# BreadBoard.net
KiCad netlist of a schematic drawn in Altium Designer
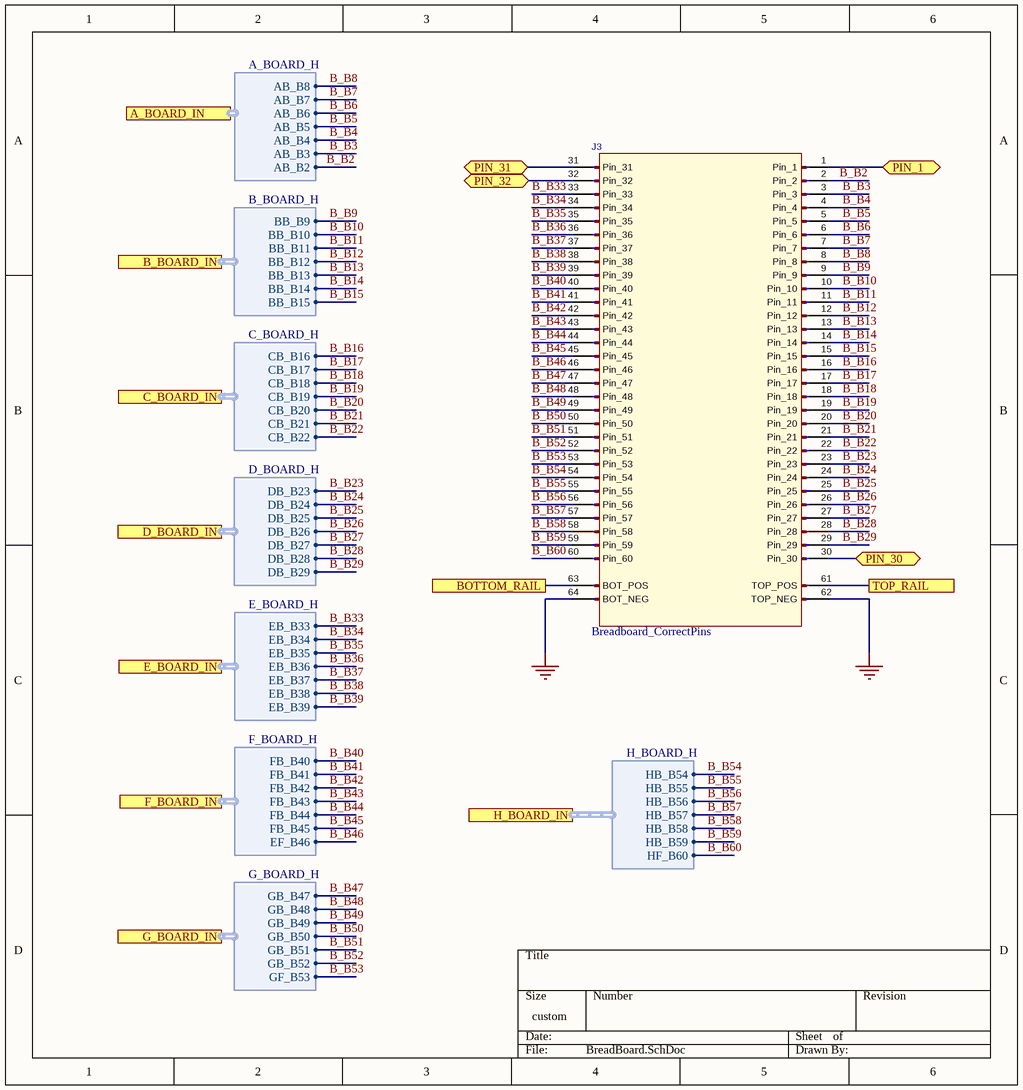
[diagram p0: BreadBoard.SchDoc]

(export (version "E")
  (design (tool "Eeschema 10.0.6"))
  (components
    (comp (ref "J3")
      (value "Breadboard_CorrectPins")
      (footprint "Breadboard_CustomClips_CorrectPins_1")
      (libsource (lib "breadboard_correctpins") (part "Breadboard_CorrectPins"))
    )
  )
  (nets
    (net (code "9") (name "/BOTTOM_RAIL") (class "Default")
      (node (ref "J3") (pin "63") (pinfunction "BOT_POS_63") (pintype "power_in"))
    )
    (net (code "10") (name "/B_B2") (class "Default")
      (node (ref "J3") (pin "2") (pinfunction "Pin_2_2") (pintype "passive"))
    )
    (net (code "11") (name "/B_B3") (class "Default")
      (node (ref "J3") (pin "3") (pinfunction "Pin_3_3") (pintype "passive"))
    )
    (net (code "12") (name "/B_B4") (class "Default")
      (node (ref "J3") (pin "4") (pinfunction "Pin_4_4") (pintype "passive"))
    )
    (net (code "13") (name "/B_B5") (class "Default")
      (node (ref "J3") (pin "5") (pinfunction "Pin_5_5") (pintype "passive"))
    )
    (net (code "14") (name "/B_B6") (class "Default")
      (node (ref "J3") (pin "6") (pinfunction "Pin_6_6") (pintype "passive"))
    )
    (net (code "15") (name "/B_B7") (class "Default")
      (node (ref "J3") (pin "7") (pinfunction "Pin_7_7") (pintype "passive"))
    )
    (net (code "16") (name "/B_B8") (class "Default")
      (node (ref "J3") (pin "8") (pinfunction "Pin_8_8") (pintype "passive"))
    )
    (net (code "17") (name "/B_B9") (class "Default")
      (node (ref "J3") (pin "9") (pinfunction "Pin_9_9") (pintype "passive"))
    )
    (net (code "18") (name "/B_B10") (class "Default")
      (node (ref "J3") (pin "10") (pinfunction "Pin_10_10") (pintype "passive"))
    )
    (net (code "19") (name "/B_B11") (class "Default")
      (node (ref "J3") (pin "11") (pinfunction "Pin_11_11") (pintype "passive"))
    )
    (net (code "20") (name "/B_B12") (class "Default")
      (node (ref "J3") (pin "12") (pinfunction "Pin_12_12") (pintype "passive"))
    )
    (net (code "21") (name "/B_B13") (class "Default")
      (node (ref "J3") (pin "13") (pinfunction "Pin_13_13") (pintype "passive"))
    )
    (net (code "22") (name "/B_B14") (class "Default")
      (node (ref "J3") (pin "14") (pinfunction "Pin_14_14") (pintype "passive"))
    )
    (net (code "23") (name "/B_B15") (class "Default")
      (node (ref "J3") (pin "15") (pinfunction "Pin_15_15") (pintype "passive"))
    )
    (net (code "24") (name "/B_B16") (class "Default")
      (node (ref "J3") (pin "16") (pinfunction "Pin_16_16") (pintype "passive"))
    )
    (net (code "25") (name "/B_B17") (class "Default")
      (node (ref "J3") (pin "17") (pinfunction "Pin_17_17") (pintype "passive"))
    )
    (net (code "26") (name "/B_B18") (class "Default")
      (node (ref "J3") (pin "18") (pinfunction "Pin_18_18") (pintype "passive"))
    )
    (net (code "27") (name "/B_B19") (class "Default")
      (node (ref "J3") (pin "19") (pinfunction "Pin_19_19") (pintype "passive"))
    )
    (net (code "28") (name "/B_B20") (class "Default")
      (node (ref "J3") (pin "20") (pinfunction "Pin_20_20") (pintype "passive"))
    )
    (net (code "29") (name "/B_B21") (class "Default")
      (node (ref "J3") (pin "21") (pinfunction "Pin_21_21") (pintype "passive"))
    )
    (net (code "30") (name "/B_B22") (class "Default")
      (node (ref "J3") (pin "22") (pinfunction "Pin_22_22") (pintype "passive"))
    )
    (net (code "31") (name "/B_B23") (class "Default")
      (node (ref "J3") (pin "23") (pinfunction "Pin_23_23") (pintype "passive"))
    )
    (net (code "32") (name "/B_B24") (class "Default")
      (node (ref "J3") (pin "24") (pinfunction "Pin_24_24") (pintype "passive"))
    )
    (net (code "33") (name "/B_B25") (class "Default")
      (node (ref "J3") (pin "25") (pinfunction "Pin_25_25") (pintype "passive"))
    )
    (net (code "34") (name "/B_B26") (class "Default")
      (node (ref "J3") (pin "26") (pinfunction "Pin_26_26") (pintype "passive"))
    )
    (net (code "35") (name "/B_B27") (class "Default")
      (node (ref "J3") (pin "27") (pinfunction "Pin_27_27") (pintype "passive"))
    )
    (net (code "36") (name "/B_B28") (class "Default")
      (node (ref "J3") (pin "28") (pinfunction "Pin_28_28") (pintype "passive"))
    )
    (net (code "37") (name "/B_B29") (class "Default")
      (node (ref "J3") (pin "29") (pinfunction "Pin_29_29") (pintype "passive"))
    )
    (net (code "38") (name "/B_B33") (class "Default")
      (node (ref "J3") (pin "33") (pinfunction "Pin_33_33") (pintype "passive"))
    )
    (net (code "39") (name "/B_B34") (class "Default")
      (node (ref "J3") (pin "34") (pinfunction "Pin_34_34") (pintype "passive"))
    )
    (net (code "40") (name "/B_B35") (class "Default")
      (node (ref "J3") (pin "35") (pinfunction "Pin_35_35") (pintype "passive"))
    )
    (net (code "41") (name "/B_B36") (class "Default")
      (node (ref "J3") (pin "36") (pinfunction "Pin_36_36") (pintype "passive"))
    )
    (net (code "42") (name "/B_B37") (class "Default")
      (node (ref "J3") (pin "37") (pinfunction "Pin_37_37") (pintype "passive"))
    )
    (net (code "43") (name "/B_B38") (class "Default")
      (node (ref "J3") (pin "38") (pinfunction "Pin_38_38") (pintype "passive"))
    )
    (net (code "44") (name "/B_B39") (class "Default")
      (node (ref "J3") (pin "39") (pinfunction "Pin_39_39") (pintype "passive"))
    )
    (net (code "45") (name "/B_B40") (class "Default")
      (node (ref "J3") (pin "40") (pinfunction "Pin_40_40") (pintype "passive"))
    )
    (net (code "46") (name "/B_B41") (class "Default")
      (node (ref "J3") (pin "41") (pinfunction "Pin_41_41") (pintype "passive"))
    )
    (net (code "47") (name "/B_B42") (class "Default")
      (node (ref "J3") (pin "42") (pinfunction "Pin_42_42") (pintype "passive"))
    )
    (net (code "48") (name "/B_B43") (class "Default")
      (node (ref "J3") (pin "43") (pinfunction "Pin_43_43") (pintype "passive"))
    )
    (net (code "49") (name "/B_B44") (class "Default")
      (node (ref "J3") (pin "44") (pinfunction "Pin_44_44") (pintype "passive"))
    )
    (net (code "50") (name "/B_B45") (class "Default")
      (node (ref "J3") (pin "45") (pinfunction "Pin_45_45") (pintype "passive"))
    )
    (net (code "51") (name "/B_B46") (class "Default")
      (node (ref "J3") (pin "46") (pinfunction "Pin_46_46") (pintype "passive"))
    )
    (net (code "52") (name "/B_B47") (class "Default")
      (node (ref "J3") (pin "47") (pinfunction "Pin_47_47") (pintype "passive"))
    )
    (net (code "53") (name "/B_B48") (class "Default")
      (node (ref "J3") (pin "48") (pinfunction "Pin_48_48") (pintype "passive"))
    )
    (net (code "54") (name "/B_B49") (class "Default")
      (node (ref "J3") (pin "49") (pinfunction "Pin_49_49") (pintype "passive"))
    )
    (net (code "55") (name "/B_B50") (class "Default")
      (node (ref "J3") (pin "50") (pinfunction "Pin_50_50") (pintype "passive"))
    )
    (net (code "56") (name "/B_B51") (class "Default")
      (node (ref "J3") (pin "51") (pinfunction "Pin_51_51") (pintype "passive"))
    )
    (net (code "57") (name "/B_B52") (class "Default")
      (node (ref "J3") (pin "52") (pinfunction "Pin_52_52") (pintype "passive"))
    )
    (net (code "58") (name "/B_B53") (class "Default")
      (node (ref "J3") (pin "53") (pinfunction "Pin_53_53") (pintype "passive"))
    )
    (net (code "59") (name "/B_B54") (class "Default")
      (node (ref "J3") (pin "54") (pinfunction "Pin_54_54") (pintype "passive"))
    )
    (net (code "60") (name "/B_B55") (class "Default")
      (node (ref "J3") (pin "55") (pinfunction "Pin_55_55") (pintype "passive"))
    )
    (net (code "61") (name "/B_B56") (class "Default")
      (node (ref "J3") (pin "56") (pinfunction "Pin_56_56") (pintype "passive"))
    )
    (net (code "62") (name "/B_B57") (class "Default")
      (node (ref "J3") (pin "57") (pinfunction "Pin_57_57") (pintype "passive"))
    )
    (net (code "63") (name "/B_B58") (class "Default")
      (node (ref "J3") (pin "58") (pinfunction "Pin_58_58") (pintype "passive"))
    )
    (net (code "64") (name "/B_B59") (class "Default")
      (node (ref "J3") (pin "59") (pinfunction "Pin_59_59") (pintype "passive"))
    )
    (net (code "65") (name "/B_B60") (class "Default")
      (node (ref "J3") (pin "60") (pinfunction "Pin_60_60") (pintype "passive"))
    )
    (net (code "66") (name "/PIN_1") (class "Default")
      (node (ref "J3") (pin "1") (pinfunction "Pin_1_1") (pintype "passive"))
    )
    (net (code "67") (name "/PIN_30") (class "Default")
      (node (ref "J3") (pin "30") (pinfunction "Pin_30_30") (pintype "passive"))
    )
    (net (code "68") (name "/PIN_31") (class "Default")
      (node (ref "J3") (pin "31") (pinfunction "Pin_31_31") (pintype "passive"))
    )
    (net (code "69") (name "/PIN_32") (class "Default")
      (node (ref "J3") (pin "32") (pinfunction "Pin_32_32") (pintype "passive"))
    )
    (net (code "70") (name "/TOP_RAIL") (class "Default")
      (node (ref "J3") (pin "61") (pinfunction "TOP_POS_61") (pintype "power_in"))
    )
    (net (code "79") (name "GND") (class "Default")
      (node (ref "J3") (pin "62") (pinfunction "TOP_NEG_62") (pintype "power_in"))
      (node (ref "J3") (pin "64") (pinfunction "BOT_NEG_64") (pintype "power_in"))
    )
  )
)
